# ArcadESP.net
KiCad netlist of a schematic drawn in EAGLE
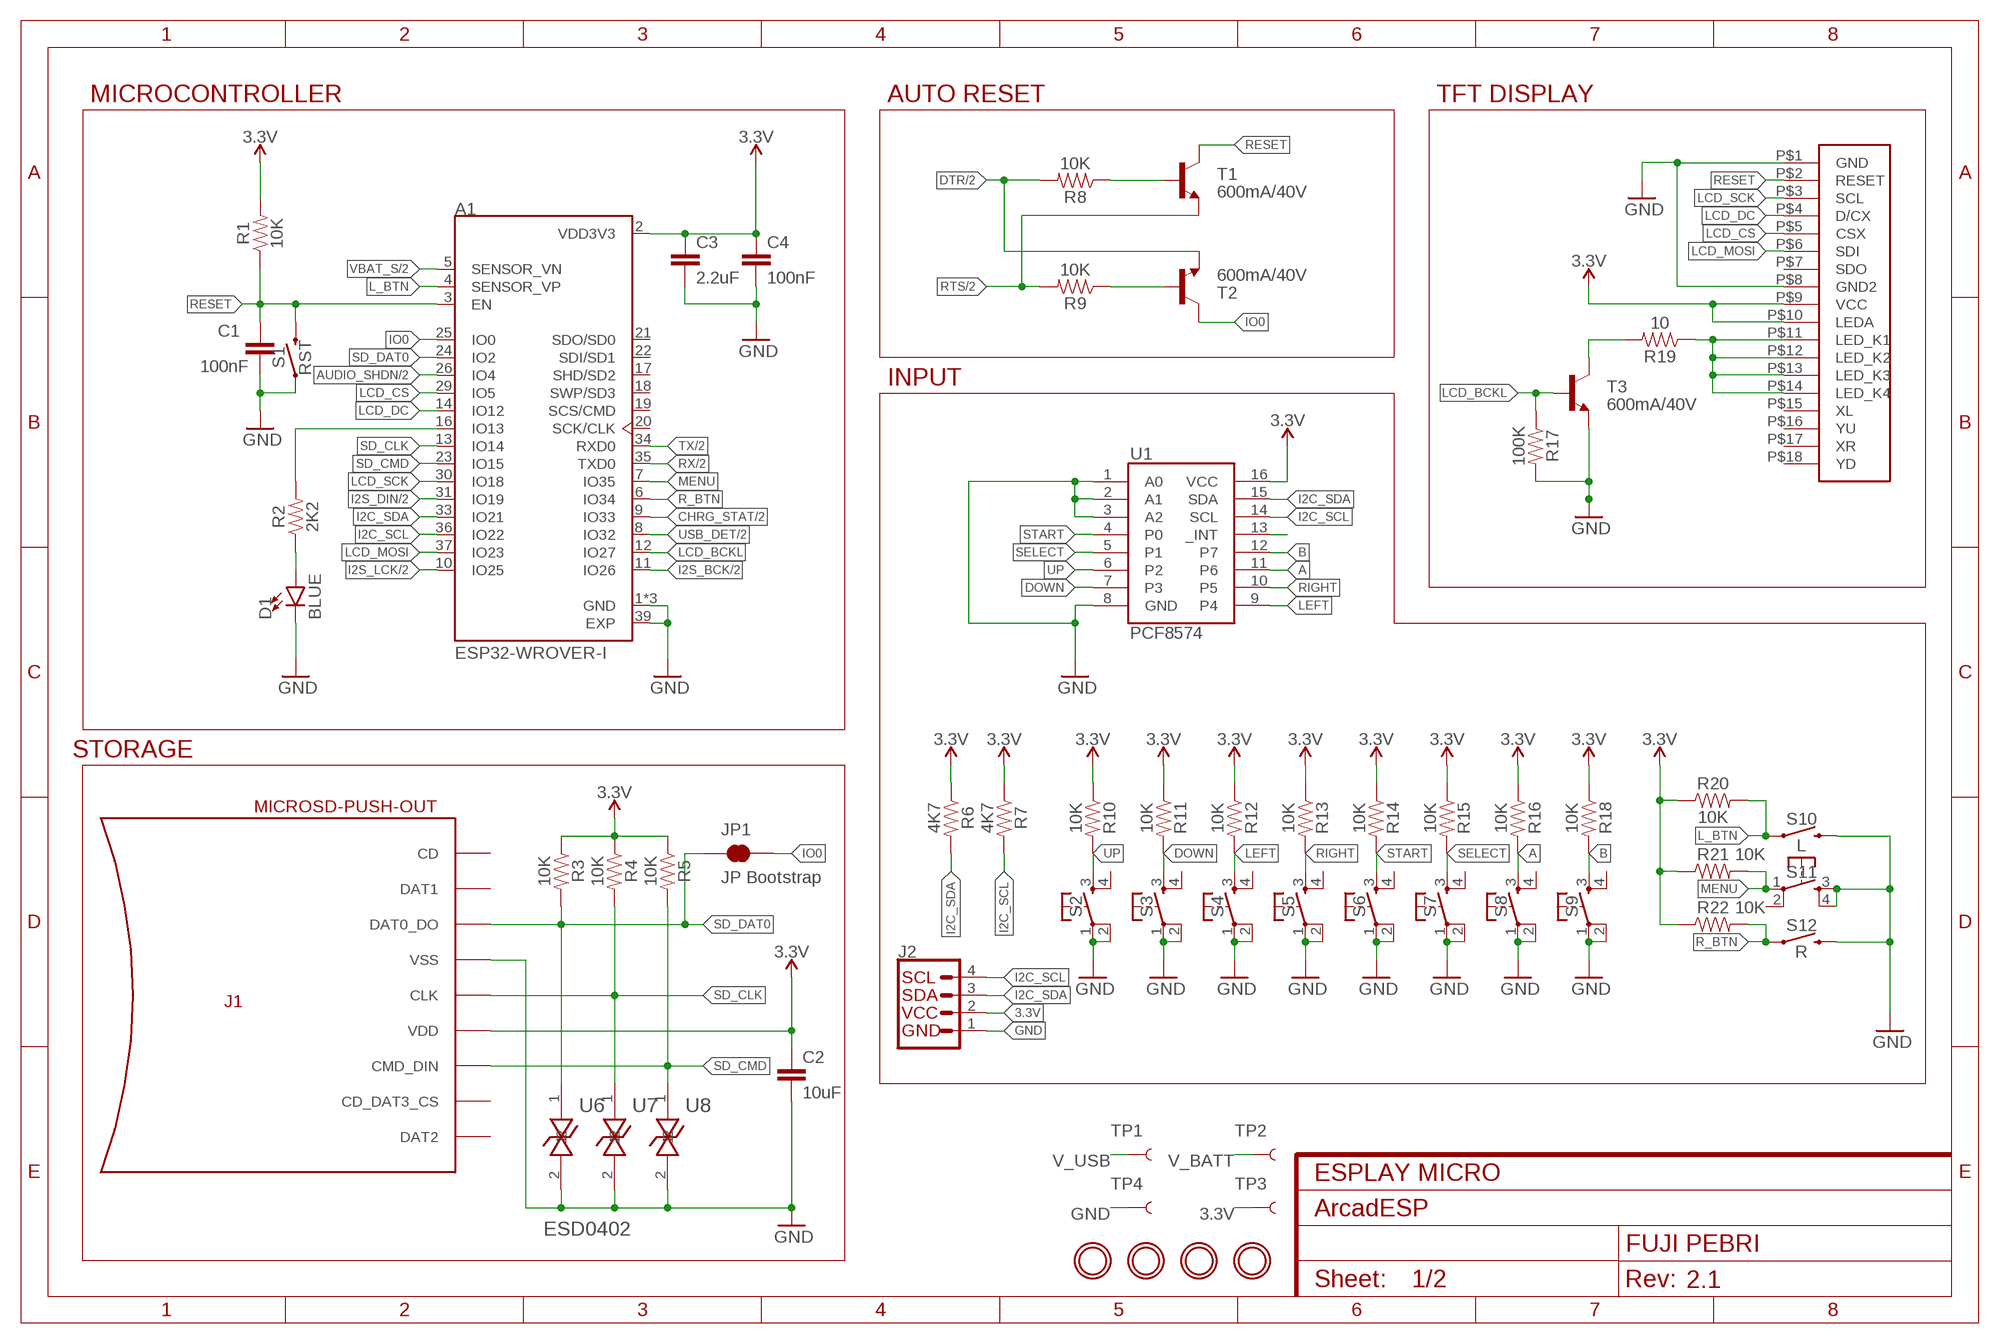
[diagram p0: schematic, sheet 1]
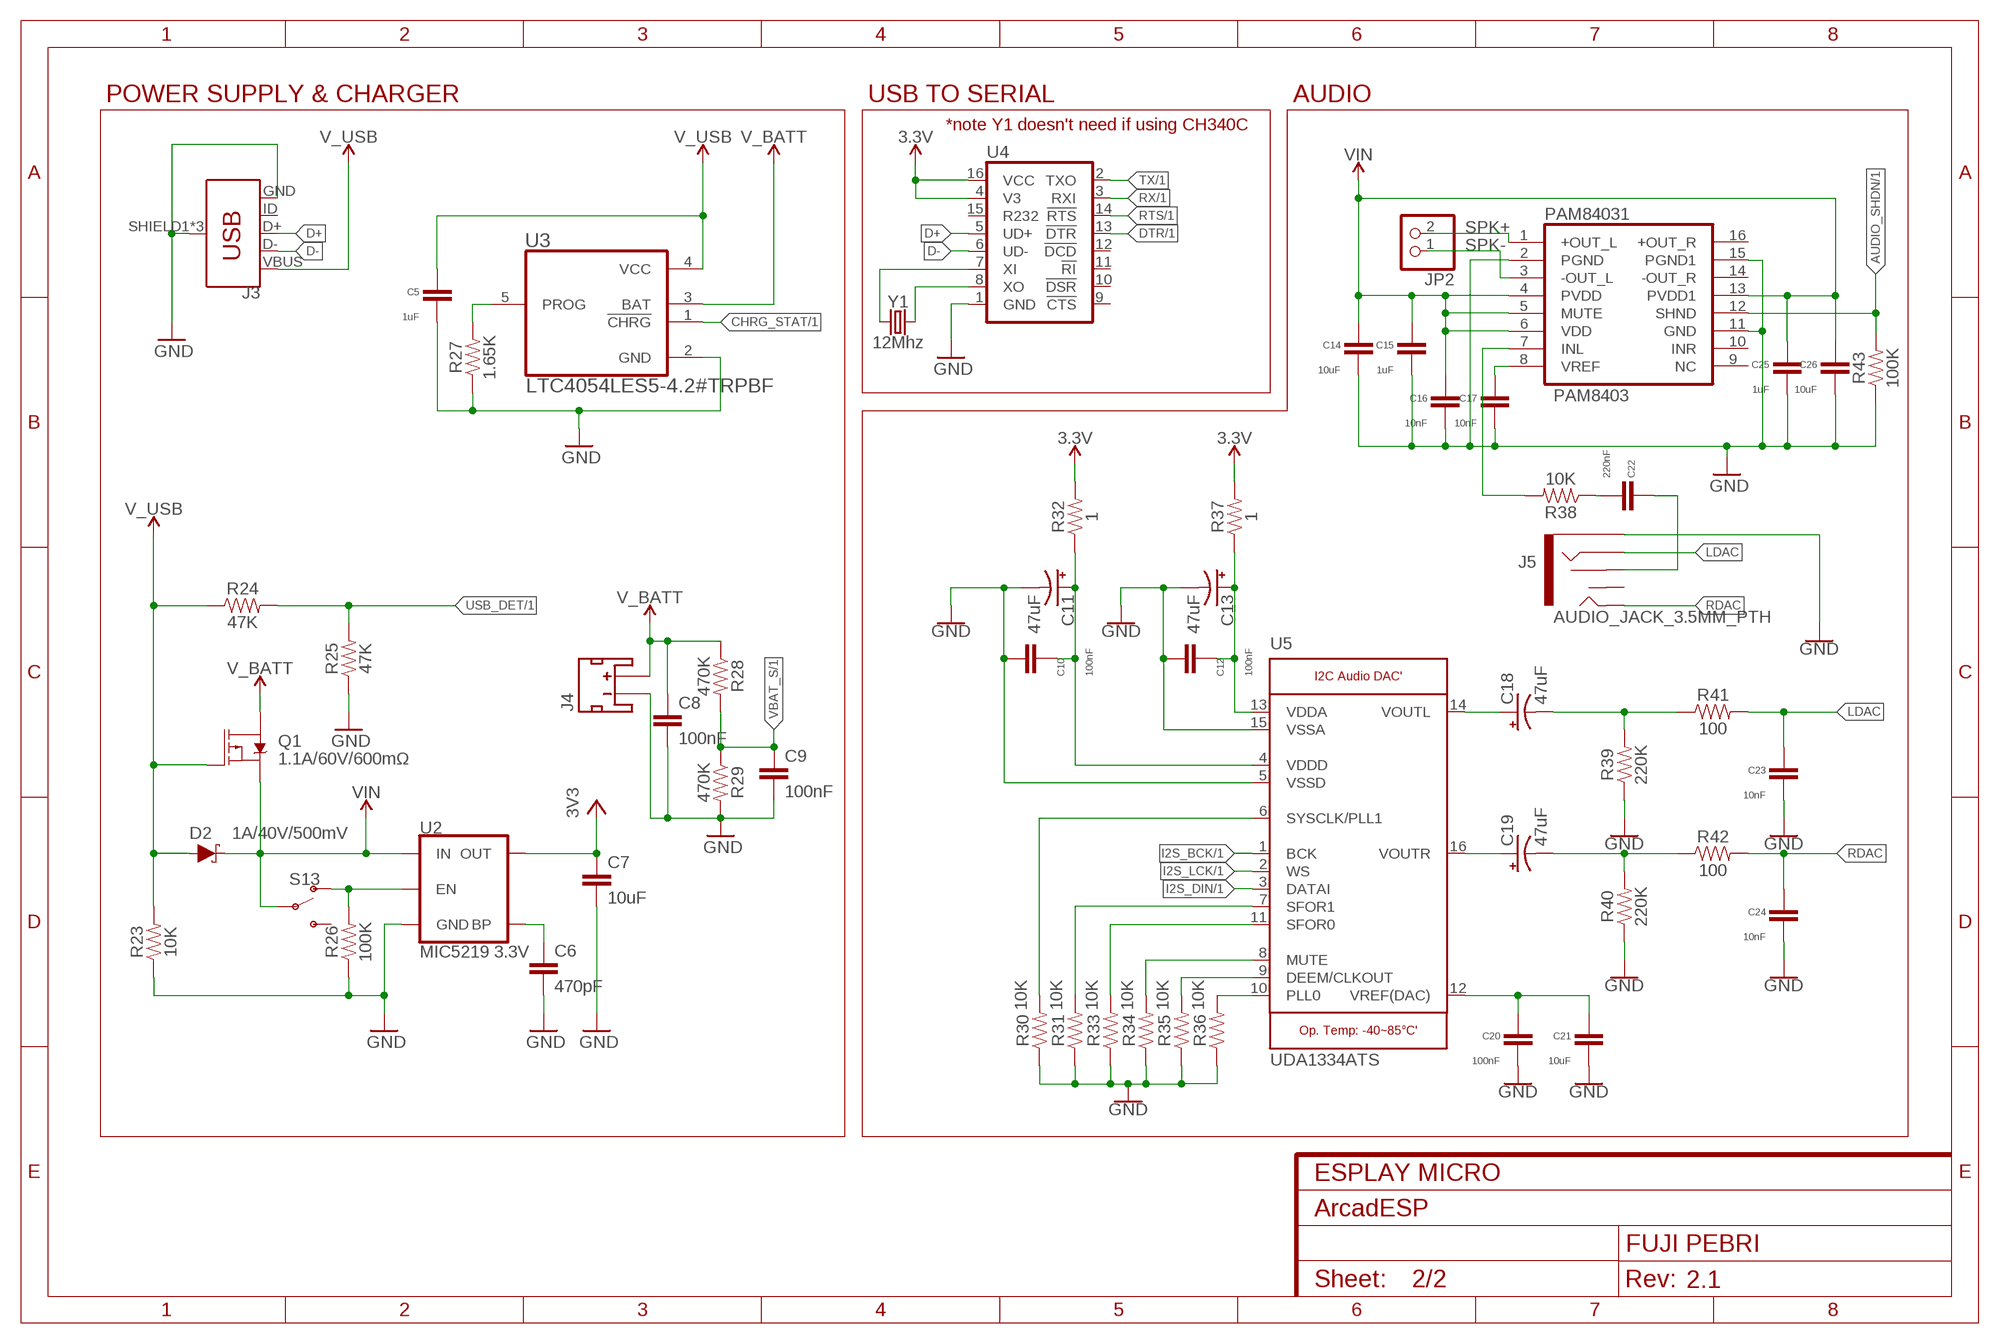
[diagram p1: schematic, sheet 2]

(export (version "E")
  (design (tool "Eeschema 10.0.6"))
  (components
    (comp (ref "C5")
      (value "1uF")
      (footprint "eagle-import:0805")
      (libsource (lib "eagle-import") (part "2.2UF-0805-25V-(+80/-20%)"))
    )
    (comp (ref "C6")
      (value "470pF")
      (footprint "eagle-import:0805")
      (libsource (lib "eagle-import") (part "2.2UF-0805-25V-(+80/-20%)"))
    )
    (comp (ref "C7")
      (value "10uF")
      (footprint "eagle-import:0805")
      (libsource (lib "eagle-import") (part "2.2UF-0805-25V-(+80/-20%)"))
    )
    (comp (ref "C8")
      (value "100nF")
      (footprint "eagle-import:0805")
      (libsource (lib "eagle-import") (part "2.2UF-0805-25V-(+80/-20%)"))
    )
    (comp (ref "C9")
      (value "100nF")
      (footprint "eagle-import:0805")
      (libsource (lib "eagle-import") (part "2.2UF-0805-25V-(+80/-20%)"))
    )
    (comp (ref "C10")
      (value "100nF")
      (footprint "eagle-import:0805")
      (libsource (lib "eagle-import") (part "2.2UF-0805-25V-(+80/-20%)"))
    )
    (comp (ref "C11")
      (value "47uF")
      (footprint "eagle-import:EIA3528")
      (libsource (lib "eagle-import") (part "47UF-POLAR-EIA3528-10V-10%"))
    )
    (comp (ref "C12")
      (value "100nF")
      (footprint "eagle-import:0805")
      (libsource (lib "eagle-import") (part "2.2UF-0805-25V-(+80/-20%)"))
    )
    (comp (ref "C13")
      (value "47uF")
      (footprint "eagle-import:EIA3528")
      (libsource (lib "eagle-import") (part "47UF-POLAR-EIA3528-10V-10%"))
    )
    (comp (ref "C14")
      (value "10uF")
      (footprint "eagle-import:0805")
      (libsource (lib "eagle-import") (part "2.2UF-0805-25V-(+80/-20%)"))
    )
    (comp (ref "C15")
      (value "1uF")
      (footprint "eagle-import:0805")
      (libsource (lib "eagle-import") (part "2.2UF-0805-25V-(+80/-20%)"))
    )
    (comp (ref "C16")
      (value "10nF")
      (footprint "eagle-import:0805")
      (libsource (lib "eagle-import") (part "2.2UF-0805-25V-(+80/-20%)"))
    )
    (comp (ref "C17")
      (value "10nF")
      (footprint "eagle-import:0805")
      (libsource (lib "eagle-import") (part "2.2UF-0805-25V-(+80/-20%)"))
    )
    (comp (ref "C18")
      (value "47uF")
      (footprint "eagle-import:EIA3528")
      (libsource (lib "eagle-import") (part "47UF-POLAR-EIA3528-10V-10%"))
    )
    (comp (ref "C19")
      (value "47uF")
      (footprint "eagle-import:EIA3528")
      (libsource (lib "eagle-import") (part "47UF-POLAR-EIA3528-10V-10%"))
    )
    (comp (ref "C20")
      (value "100nF")
      (footprint "eagle-import:0805")
      (libsource (lib "eagle-import") (part "2.2UF-0805-25V-(+80/-20%)"))
    )
    (comp (ref "C21")
      (value "10uF")
      (footprint "eagle-import:0805")
      (libsource (lib "eagle-import") (part "2.2UF-0805-25V-(+80/-20%)"))
    )
    (comp (ref "C22")
      (value "220nF")
      (footprint "eagle-import:0805")
      (libsource (lib "eagle-import") (part "2.2UF-0805-25V-(+80/-20%)"))
    )
    (comp (ref "C23")
      (value "10nF")
      (footprint "eagle-import:0805")
      (libsource (lib "eagle-import") (part "2.2UF-0805-25V-(+80/-20%)"))
    )
    (comp (ref "C24")
      (value "10nF")
      (footprint "eagle-import:0805")
      (libsource (lib "eagle-import") (part "2.2UF-0805-25V-(+80/-20%)"))
    )
    (comp (ref "C25")
      (value "1uF")
      (footprint "eagle-import:0805")
      (libsource (lib "eagle-import") (part "2.2UF-0805-25V-(+80/-20%)"))
    )
    (comp (ref "C26")
      (value "10uF")
      (footprint "eagle-import:0805")
      (libsource (lib "eagle-import") (part "2.2UF-0805-25V-(+80/-20%)"))
    )
    (comp (ref "D2")
      (value "1A/40V/500mV")
      (footprint "eagle-import:SMA-DIODE")
      (libsource (lib "eagle-import") (part "DIODE-SCHOTTKY-SS14"))
    )
    (comp (ref "J3")
      (value "USB_MICRO-B_FEMALE-SMT")
      (footprint "eagle-import:USB-B-MICRO-SMD")
      (libsource (lib "eagle-import") (part "USB_MICRO-B_FEMALE-SMT"))
    )
    (comp (ref "J4")
      (value "JST_2MM_MALE")
      (footprint "eagle-import:JST-2-SMD")
      (libsource (lib "eagle-import") (part "JST_2MM_MALE"))
    )
    (comp (ref "J5")
      (value "AUDIO_JACK_3.5MM_PTH")
      (footprint "eagle-import:AUDIO-JACK")
      (libsource (lib "eagle-import") (part "AUDIO_JACK_3.5MM_PTH"))
    )
    (comp (ref "JP2")
      (value "PINHD-1X2_2.00")
      (footprint "eagle-import:1X02M")
      (libsource (lib "eagle-import") (part "PINHD-1X2_2.00"))
    )
    (comp (ref "PAM84031")
      (value "PAM8403")
      (footprint "eagle-import:SOP-16")
      (libsource (lib "eagle-import") (part "PAM8403"))
    )
    (comp (ref "Q1")
      (value "1.1A/60V/600mΩ")
      (footprint "eagle-import:SOT23-3")
      (libsource (lib "eagle-import") (part "MOSFET_PCH-SI2309DS"))
    )
    (comp (ref "R23")
      (value "10K")
      (footprint "eagle-import:0805")
      (libsource (lib "eagle-import") (part "0.22OHM-0805-1/4W-1%"))
    )
    (comp (ref "R24")
      (value "47K")
      (footprint "eagle-import:0805")
      (libsource (lib "eagle-import") (part "0.22OHM-0805-1/4W-1%"))
    )
    (comp (ref "R25")
      (value "47K")
      (footprint "eagle-import:0805")
      (libsource (lib "eagle-import") (part "0.22OHM-0805-1/4W-1%"))
    )
    (comp (ref "R26")
      (value "100K")
      (footprint "eagle-import:0805")
      (libsource (lib "eagle-import") (part "0.22OHM-0805-1/4W-1%"))
    )
    (comp (ref "R27")
      (value "1.65K")
      (footprint "eagle-import:0805")
      (libsource (lib "eagle-import") (part "0.3OHM-0805-1/8W-1%"))
    )
    (comp (ref "R28")
      (value "470K")
      (footprint "eagle-import:0805")
      (libsource (lib "eagle-import") (part "0.22OHM-0805-1/4W-1%"))
    )
    (comp (ref "R29")
      (value "470K")
      (footprint "eagle-import:0805")
      (libsource (lib "eagle-import") (part "0.22OHM-0805-1/4W-1%"))
    )
    (comp (ref "R30")
      (value "10K")
      (footprint "eagle-import:0805")
      (libsource (lib "eagle-import") (part "0.3OHM-0805-1/8W-1%"))
    )
    (comp (ref "R31")
      (value "10K")
      (footprint "eagle-import:0805")
      (libsource (lib "eagle-import") (part "0.3OHM-0805-1/8W-1%"))
    )
    (comp (ref "R32")
      (value "1")
      (footprint "eagle-import:0805")
      (libsource (lib "eagle-import") (part "0.3OHM-0805-1/8W-1%"))
    )
    (comp (ref "R33")
      (value "10K")
      (footprint "eagle-import:0805")
      (libsource (lib "eagle-import") (part "0.3OHM-0805-1/8W-1%"))
    )
    (comp (ref "R34")
      (value "10K")
      (footprint "eagle-import:0805")
      (libsource (lib "eagle-import") (part "0.3OHM-0805-1/8W-1%"))
    )
    (comp (ref "R35")
      (value "10K")
      (footprint "eagle-import:0805")
      (libsource (lib "eagle-import") (part "0.3OHM-0805-1/8W-1%"))
    )
    (comp (ref "R36")
      (value "10K")
      (footprint "eagle-import:0805")
      (libsource (lib "eagle-import") (part "0.3OHM-0805-1/8W-1%"))
    )
    (comp (ref "R37")
      (value "1")
      (footprint "eagle-import:0805")
      (libsource (lib "eagle-import") (part "0.3OHM-0805-1/8W-1%"))
    )
    (comp (ref "R38")
      (value "10K")
      (footprint "eagle-import:0805")
      (libsource (lib "eagle-import") (part "0.3OHM-0805-1/8W-1%"))
    )
    (comp (ref "R39")
      (value "220K")
      (footprint "eagle-import:0805")
      (libsource (lib "eagle-import") (part "0.3OHM-0805-1/8W-1%"))
    )
    (comp (ref "R40")
      (value "220K")
      (footprint "eagle-import:0805")
      (libsource (lib "eagle-import") (part "0.3OHM-0805-1/8W-1%"))
    )
    (comp (ref "R41")
      (value "100")
      (footprint "eagle-import:0805")
      (libsource (lib "eagle-import") (part "0.3OHM-0805-1/8W-1%"))
    )
    (comp (ref "R42")
      (value "100")
      (footprint "eagle-import:0805")
      (libsource (lib "eagle-import") (part "0.3OHM-0805-1/8W-1%"))
    )
    (comp (ref "R43")
      (value "100K")
      (footprint "eagle-import:0805")
      (libsource (lib "eagle-import") (part "0.3OHM-0805-1/8W-1%"))
    )
    (comp (ref "S13")
      (value "SWITCH-SPDT-SMD-RIGHT-ANGLE")
      (footprint "eagle-import:SWITCH_SPST_SMD_A")
      (libsource (lib "eagle-import") (part "SWITCH-SPDT-SMD-RIGHT-ANGLE"))
    )
    (comp (ref "U2")
      (value "MIC5219 3.3V")
      (footprint "eagle-import:SOT23-5")
      (libsource (lib "eagle-import") (part "V_REG_MIC52193.3V"))
    )
    (comp (ref "U3")
      (value "LTC4054LES5-4.2#TRPBF")
      (footprint "eagle-import:SOT95P280X100-5N")
      (fields
        (field (name "DIGI-KEY_PART_NUMBER") "LTC4054LES5-4.2#TRPBFCT-ND")
        (field (name "MF") "Linear Technology/Analog")
      )
      (libsource (lib "eagle-import") (part "LTC4054LES5-4.2#TRPBF"))
    )
    (comp (ref "U4")
      (value "CH340G")
      (footprint "eagle-import:SO016")
      (libsource (lib "eagle-import") (part "CH340GSMD"))
    )
    (comp (ref "U5")
      (value "UDA1334ATS")
      (footprint "eagle-import:MICROBUILDER_SSOP16_4.4MM")
      (libsource (lib "eagle-import") (part "MICROBUILDER_AUDIO_I2S_UDA1334{dblquote}{dblquote}"))
    )
    (comp (ref "Y1")
      (value "12Mhz")
      (footprint "eagle-import:CRYSTAL-SMD-5X3.2-4PAD")
      (libsource (lib "eagle-import") (part "CRYSTALSMD-5X3.2-4PAD"))
    )
    (comp (ref "A1")
      (value "ESP32-WROVER-I")
      (footprint "eagle-import:XCVR_ESP32-WROVER-I")
      (fields (field (name "MF") "Espressif Systems"))
      (libsource (lib "eagle-import") (part "ESP32-WROVER-I"))
    )
    (comp (ref "C1")
      (value "100nF")
      (footprint "eagle-import:0805")
      (libsource (lib "eagle-import") (part "2.2UF-0805-25V-(+80/-20%)"))
    )
    (comp (ref "C2")
      (value "10uF")
      (footprint "eagle-import:0805")
      (libsource (lib "eagle-import") (part "2.2UF-0805-25V-(+80/-20%)"))
    )
    (comp (ref "C3")
      (value "2.2uF")
      (footprint "eagle-import:0805")
      (libsource (lib "eagle-import") (part "2.2UF-0805-25V-(+80/-20%)"))
    )
    (comp (ref "C4")
      (value "100nF")
      (footprint "eagle-import:0805")
      (libsource (lib "eagle-import") (part "2.2UF-0805-25V-(+80/-20%)"))
    )
    (comp (ref "D1")
      (value "BLUE")
      (footprint "eagle-import:LED-0603")
      (libsource (lib "eagle-import") (part "LED-BLUE0603"))
    )
    (comp (ref "H1")
      (value "MICROBUILDER_MOUNTINGHOLE3.0THIN")
      (footprint "eagle-import:MICROBUILDER_MOUNTINGHOLE_3.0_PLATEDTHIN")
      (libsource (lib "eagle-import") (part "MICROBUILDER_MOUNTINGHOLE3.0THIN"))
    )
    (comp (ref "H2")
      (value "MICROBUILDER_MOUNTINGHOLE3.0THIN")
      (footprint "eagle-import:MICROBUILDER_MOUNTINGHOLE_3.0_PLATEDTHIN")
      (libsource (lib "eagle-import") (part "MICROBUILDER_MOUNTINGHOLE3.0THIN"))
    )
    (comp (ref "H3")
      (value "MICROBUILDER_MOUNTINGHOLE3.0THIN")
      (footprint "eagle-import:MICROBUILDER_MOUNTINGHOLE_3.0_PLATEDTHIN")
      (libsource (lib "eagle-import") (part "MICROBUILDER_MOUNTINGHOLE3.0THIN"))
    )
    (comp (ref "H4")
      (value "MICROBUILDER_MOUNTINGHOLE3.0THIN")
      (footprint "eagle-import:MICROBUILDER_MOUNTINGHOLE_3.0_PLATEDTHIN")
      (libsource (lib "eagle-import") (part "MICROBUILDER_MOUNTINGHOLE3.0THIN"))
    )
    (comp (ref "J1")
      (value "MICROSD-PUSH-OUT")
      (footprint "eagle-import:MICROSD-PUSH-OUT")
      (libsource (lib "eagle-import") (part "MICROSD-PUSH-OUT"))
    )
    (comp (ref "J2")
      (value "QWIIC_CONNECTORJS-1MM")
      (footprint "eagle-import:1X04_1MM_RA")
      (libsource (lib "eagle-import") (part "QWIIC_CONNECTORJS-1MM"))
    )
    (comp (ref "JP1")
      (value "JP Bootstrap")
      (footprint "eagle-import:SMT-JUMPER_2_NC_TRACE_NO-SILK")
      (libsource (lib "eagle-import") (part "JUMPER-SMT_2_NC_TRACE_NO-SILK"))
    )
    (comp (ref "LCD1")
      (value "ILI9341-2.4")
      (footprint "eagle-import:ILI9341-2.4")
      (libsource (lib "eagle-import") (part "ILI9341-2.4"))
    )
    (comp (ref "R1")
      (value "10K")
      (footprint "eagle-import:0805")
      (libsource (lib "eagle-import") (part "0.22OHM-0805-1/4W-1%"))
    )
    (comp (ref "R2")
      (value "2K2")
      (footprint "eagle-import:0805")
      (libsource (lib "eagle-import") (part "0.22OHM-0805-1/4W-1%"))
    )
    (comp (ref "R3")
      (value "10K")
      (footprint "eagle-import:0805")
      (libsource (lib "eagle-import") (part "0.22OHM-0805-1/4W-1%"))
    )
    (comp (ref "R4")
      (value "10K")
      (footprint "eagle-import:0805")
      (libsource (lib "eagle-import") (part "0.22OHM-0805-1/4W-1%"))
    )
    (comp (ref "R5")
      (value "10K")
      (footprint "eagle-import:0805")
      (libsource (lib "eagle-import") (part "0.22OHM-0805-1/4W-1%"))
    )
    (comp (ref "R6")
      (value "4K7")
      (footprint "eagle-import:0805")
      (libsource (lib "eagle-import") (part "0.22OHM-0805-1/4W-1%"))
    )
    (comp (ref "R7")
      (value "4K7")
      (footprint "eagle-import:0805")
      (libsource (lib "eagle-import") (part "0.22OHM-0805-1/4W-1%"))
    )
    (comp (ref "R8")
      (value "10K")
      (footprint "eagle-import:0805")
      (libsource (lib "eagle-import") (part "0.22OHM-0805-1/4W-1%"))
    )
    (comp (ref "R9")
      (value "10K")
      (footprint "eagle-import:0805")
      (libsource (lib "eagle-import") (part "0.22OHM-0805-1/4W-1%"))
    )
    (comp (ref "R10")
      (value "10K")
      (footprint "eagle-import:0805")
      (libsource (lib "eagle-import") (part "0.22OHM-0805-1/4W-1%"))
    )
    (comp (ref "R11")
      (value "10K")
      (footprint "eagle-import:0805")
      (libsource (lib "eagle-import") (part "0.22OHM-0805-1/4W-1%"))
    )
    (comp (ref "R12")
      (value "10K")
      (footprint "eagle-import:0805")
      (libsource (lib "eagle-import") (part "0.22OHM-0805-1/4W-1%"))
    )
    (comp (ref "R13")
      (value "10K")
      (footprint "eagle-import:0805")
      (libsource (lib "eagle-import") (part "0.22OHM-0805-1/4W-1%"))
    )
    (comp (ref "R14")
      (value "10K")
      (footprint "eagle-import:0805")
      (libsource (lib "eagle-import") (part "0.22OHM-0805-1/4W-1%"))
    )
    (comp (ref "R15")
      (value "10K")
      (footprint "eagle-import:0805")
      (libsource (lib "eagle-import") (part "0.22OHM-0805-1/4W-1%"))
    )
    (comp (ref "R16")
      (value "10K")
      (footprint "eagle-import:0805")
      (libsource (lib "eagle-import") (part "0.22OHM-0805-1/4W-1%"))
    )
    (comp (ref "R17")
      (value "100K")
      (footprint "eagle-import:0805")
      (libsource (lib "eagle-import") (part "0.22OHM-0805-1/4W-1%"))
    )
    (comp (ref "R18")
      (value "10K")
      (footprint "eagle-import:0805")
      (libsource (lib "eagle-import") (part "0.22OHM-0805-1/4W-1%"))
    )
    (comp (ref "R19")
      (value "10")
      (footprint "eagle-import:0805")
      (libsource (lib "eagle-import") (part "0.22OHM-0805-1/4W-1%"))
    )
    (comp (ref "R20")
      (value "10K")
      (footprint "eagle-import:0805")
      (libsource (lib "eagle-import") (part "0.22OHM-0805-1/4W-1%"))
    )
    (comp (ref "R21")
      (value "10K")
      (footprint "eagle-import:0805")
      (libsource (lib "eagle-import") (part "0.22OHM-0805-1/4W-1%"))
    )
    (comp (ref "R22")
      (value "10K")
      (footprint "eagle-import:0805")
      (libsource (lib "eagle-import") (part "0.22OHM-0805-1/4W-1%"))
    )
    (comp (ref "S1")
      (value "RST")
      (footprint "eagle-import:TACTILE_SWITCH_SMD_4.6X2.8MM")
      (libsource (lib "eagle-import") (part "MOMENTARY-SWITCH-SPST-SMD-4.6X2.8MM"))
    )
    (comp (ref "S2")
      (value "MOMENTARY-SWITCH-SPST-2-SMD-5.2MM")
      (footprint "eagle-import:TACTILE_SWITCH_SMD_5.2MM")
      (libsource (lib "eagle-import") (part "MOMENTARY-SWITCH-SPST-2-SMD-5.2MM"))
    )
    (comp (ref "S3")
      (value "MOMENTARY-SWITCH-SPST-2-SMD-5.2MM")
      (footprint "eagle-import:TACTILE_SWITCH_SMD_5.2MM")
      (libsource (lib "eagle-import") (part "MOMENTARY-SWITCH-SPST-2-SMD-5.2MM"))
    )
    (comp (ref "S4")
      (value "MOMENTARY-SWITCH-SPST-2-SMD-5.2MM")
      (footprint "eagle-import:TACTILE_SWITCH_SMD_5.2MM")
      (libsource (lib "eagle-import") (part "MOMENTARY-SWITCH-SPST-2-SMD-5.2MM"))
    )
    (comp (ref "S5")
      (value "MOMENTARY-SWITCH-SPST-2-SMD-5.2MM")
      (footprint "eagle-import:TACTILE_SWITCH_SMD_5.2MM")
      (libsource (lib "eagle-import") (part "MOMENTARY-SWITCH-SPST-2-SMD-5.2MM"))
    )
    (comp (ref "S6")
      (value "MOMENTARY-SWITCH-SPST-2-SMD-5.2MM")
      (footprint "eagle-import:TACTILE_SWITCH_SMD_5.2MM")
      (libsource (lib "eagle-import") (part "MOMENTARY-SWITCH-SPST-2-SMD-5.2MM"))
    )
    (comp (ref "S7")
      (value "MOMENTARY-SWITCH-SPST-2-SMD-5.2MM")
      (footprint "eagle-import:TACTILE_SWITCH_SMD_5.2MM")
      (libsource (lib "eagle-import") (part "MOMENTARY-SWITCH-SPST-2-SMD-5.2MM"))
    )
    (comp (ref "S8")
      (value "MOMENTARY-SWITCH-SPST-2-SMD-5.2MM")
      (footprint "eagle-import:TACTILE_SWITCH_SMD_5.2MM")
      (libsource (lib "eagle-import") (part "MOMENTARY-SWITCH-SPST-2-SMD-5.2MM"))
    )
    (comp (ref "S9")
      (value "MOMENTARY-SWITCH-SPST-2-SMD-5.2MM")
      (footprint "eagle-import:TACTILE_SWITCH_SMD_5.2MM")
      (libsource (lib "eagle-import") (part "MOMENTARY-SWITCH-SPST-2-SMD-5.2MM"))
    )
    (comp (ref "S10")
      (value "L")
      (footprint "eagle-import:TACTILE_SWITCH_PTH_RIGHT_ANGLE_KIT")
      (libsource (lib "eagle-import") (part "MOMENTARY-SWITCH-SPST-PTH-RIGHT-ANGLE-KIT"))
    )
    (comp (ref "S11")
      (value "MOMENTARY-SWITCH-SPST-2-SMD-5.2MM")
      (footprint "eagle-import:TACTILE_SWITCH_SMD_5.2MM")
      (libsource (lib "eagle-import") (part "MOMENTARY-SWITCH-SPST-2-SMD-5.2MM"))
    )
    (comp (ref "S12")
      (value "R")
      (footprint "eagle-import:TACTILE_SWITCH_PTH_RIGHT_ANGLE_KIT")
      (libsource (lib "eagle-import") (part "MOMENTARY-SWITCH-SPST-PTH-RIGHT-ANGLE-KIT"))
    )
    (comp (ref "T1")
      (value "600mA/40V")
      (footprint "eagle-import:SOT23-3")
      (libsource (lib "eagle-import") (part "TRANS_NPN-MMBT2222AL"))
    )
    (comp (ref "T2")
      (value "600mA/40V")
      (footprint "eagle-import:SOT23-3")
      (libsource (lib "eagle-import") (part "TRANS_NPN-MMBT2222AL"))
    )
    (comp (ref "T3")
      (value "600mA/40V")
      (footprint "eagle-import:SOT23-3")
      (libsource (lib "eagle-import") (part "TRANS_NPN-MMBT2222AL"))
    )
    (comp (ref "TP1")
      (value "TEST-POINT3")
      (footprint "eagle-import:PAD.03X.03")
      (libsource (lib "eagle-import") (part "TEST-POINT3"))
    )
    (comp (ref "TP2")
      (value "TEST-POINT3")
      (footprint "eagle-import:PAD.03X.03")
      (libsource (lib "eagle-import") (part "TEST-POINT3"))
    )
    (comp (ref "TP3")
      (value "TEST-POINT3")
      (footprint "eagle-import:PAD.03X.03")
      (libsource (lib "eagle-import") (part "TEST-POINT3"))
    )
    (comp (ref "TP4")
      (value "TEST-POINT3")
      (footprint "eagle-import:PAD.03X.03")
      (libsource (lib "eagle-import") (part "TEST-POINT3"))
    )
    (comp (ref "U1")
      (value "PCF8574")
      (footprint "eagle-import:SO16")
      (fields (field (name "MF") "Texas Instruments"))
      (libsource (lib "eagle-import") (part "PCF8574"))
    )
    (comp (ref "U6")
      (value "ESD0402")
      (footprint "eagle-import:ESD0402")
      (libsource (lib "eagle-import") (part "ESD0402"))
    )
    (comp (ref "U7")
      (value "ESD0402")
      (footprint "eagle-import:ESD0402")
      (libsource (lib "eagle-import") (part "ESD0402"))
    )
    (comp (ref "U8")
      (value "ESD0402")
      (footprint "eagle-import:ESD0402")
      (libsource (lib "eagle-import") (part "ESD0402"))
    )
  )
  (nets
    (net (code "1") (name "3.3V") (class "Default")
      (node (ref "A1") (pin "2") (pinfunction "VDD3V3_2") (pintype "power_in"))
      (node (ref "C2") (pin "1") (pinfunction "1_1") (pintype "passive"))
      (node (ref "C3") (pin "1") (pinfunction "1_1") (pintype "passive"))
      (node (ref "C4") (pin "1") (pinfunction "1_1") (pintype "passive"))
      (node (ref "C7") (pin "1") (pinfunction "1_1") (pintype "passive"))
      (node (ref "J1") (pin "4") (pinfunction "VDD_4") (pintype "bidirectional"))
      (node (ref "J2") (pin "2") (pinfunction "2_2") (pintype "power_in"))
      (node (ref "LCD1") (pin "P$10") (pinfunction "LEDA_P$10") (pintype "bidirectional"))
      (node (ref "LCD1") (pin "P$9") (pinfunction "VCC_P$9") (pintype "bidirectional"))
      (node (ref "R1") (pin "2") (pinfunction "2_2") (pintype "passive"))
      (node (ref "R10") (pin "1") (pinfunction "1_1") (pintype "passive"))
      (node (ref "R11") (pin "1") (pinfunction "1_1") (pintype "passive"))
      (node (ref "R12") (pin "1") (pinfunction "1_1") (pintype "passive"))
      (node (ref "R13") (pin "1") (pinfunction "1_1") (pintype "passive"))
      (node (ref "R14") (pin "1") (pinfunction "1_1") (pintype "passive"))
      (node (ref "R15") (pin "1") (pinfunction "1_1") (pintype "passive"))
      (node (ref "R16") (pin "1") (pinfunction "1_1") (pintype "passive"))
      (node (ref "R18") (pin "1") (pinfunction "1_1") (pintype "passive"))
      (node (ref "R20") (pin "1") (pinfunction "1_1") (pintype "passive"))
      (node (ref "R21") (pin "1") (pinfunction "1_1") (pintype "passive"))
      (node (ref "R22") (pin "1") (pinfunction "1_1") (pintype "passive"))
      (node (ref "R3") (pin "1") (pinfunction "1_1") (pintype "passive"))
      (node (ref "R32") (pin "2") (pinfunction "2_2") (pintype "passive"))
      (node (ref "R37") (pin "2") (pinfunction "2_2") (pintype "passive"))
      (node (ref "R4") (pin "1") (pinfunction "1_1") (pintype "passive"))
      (node (ref "R5") (pin "1") (pinfunction "1_1") (pintype "passive"))
      (node (ref "R6") (pin "1") (pinfunction "1_1") (pintype "passive"))
      (node (ref "R7") (pin "1") (pinfunction "1_1") (pintype "passive"))
      (node (ref "TP3") (pin "P$1") (pinfunction "1_P$1") (pintype "bidirectional"))
      (node (ref "U1") (pin "16") (pinfunction "VCC_16") (pintype "bidirectional"))
      (node (ref "U2") (pin "5") (pinfunction "OUT_5") (pintype "passive"))
      (node (ref "U4") (pin "16") (pinfunction "VCC_16") (pintype "bidirectional"))
      (node (ref "U4") (pin "4") (pinfunction "V3_4") (pintype "bidirectional"))
    )
    (net (code "2") (name "A") (class "Default")
      (node (ref "R16") (pin "2") (pinfunction "2_2") (pintype "passive"))
      (node (ref "S8") (pin "3") (pinfunction "3_3") (pintype "passive"))
      (node (ref "U1") (pin "11") (pinfunction "P6_11") (pintype "bidirectional"))
    )
    (net (code "3") (name "AUDIO_SHDN") (class "Default")
      (node (ref "A1") (pin "26") (pinfunction "IO4_26") (pintype "bidirectional"))
      (node (ref "PAM84031") (pin "12") (pinfunction "SHND_12") (pintype "output"))
      (node (ref "R43") (pin "2") (pinfunction "2_2") (pintype "passive"))
    )
    (net (code "4") (name "B") (class "Default")
      (node (ref "R18") (pin "2") (pinfunction "2_2") (pintype "passive"))
      (node (ref "S9") (pin "3") (pinfunction "3_3") (pintype "passive"))
      (node (ref "U1") (pin "12") (pinfunction "P7_12") (pintype "bidirectional"))
    )
    (net (code "5") (name "CHRG_STAT") (class "Default")
      (node (ref "A1") (pin "9") (pinfunction "IO33_9") (pintype "bidirectional"))
      (node (ref "U3") (pin "1") (pinfunction "~{CHRG}_1") (pintype "output"))
    )
    (net (code "6") (name "D+") (class "Default")
      (node (ref "J3") (pin "D+") (pinfunction "D+_D+") (pintype "bidirectional"))
      (node (ref "U4") (pin "5") (pinfunction "UD+_5") (pintype "bidirectional"))
    )
    (net (code "7") (name "D-") (class "Default")
      (node (ref "J3") (pin "D-") (pinfunction "D-_D-") (pintype "bidirectional"))
      (node (ref "U4") (pin "6") (pinfunction "UD-_6") (pintype "bidirectional"))
    )
    (net (code "8") (name "DOWN") (class "Default")
      (node (ref "R11") (pin "2") (pinfunction "2_2") (pintype "passive"))
      (node (ref "S3") (pin "3") (pinfunction "3_3") (pintype "passive"))
      (node (ref "U1") (pin "7") (pinfunction "P3_7") (pintype "bidirectional"))
    )
    (net (code "9") (name "DTR") (class "Default")
      (node (ref "R8") (pin "2") (pinfunction "2_2") (pintype "passive"))
      (node (ref "T2") (pin "2") (pinfunction "E_2") (pintype "passive"))
      (node (ref "U4") (pin "13") (pinfunction "~{DTR}_13") (pintype "bidirectional"))
    )
    (net (code "10") (name "GND") (class "Default")
      (node (ref "A1") (pin "1") (pinfunction "GND_1") (pintype "power_in"))
      (node (ref "A1") (pin "15") (pinfunction "GND_15") (pintype "power_in"))
      (node (ref "A1") (pin "38") (pinfunction "GND_38") (pintype "power_in"))
      (node (ref "A1") (pin "39") (pinfunction "EXP_39") (pintype "power_in"))
      (node (ref "C1") (pin "2") (pinfunction "2_2") (pintype "passive"))
      (node (ref "C10") (pin "1") (pinfunction "1_1") (pintype "passive"))
      (node (ref "C11") (pin "C") (pinfunction "-_C") (pintype "passive"))
      (node (ref "C12") (pin "1") (pinfunction "1_1") (pintype "passive"))
      (node (ref "C13") (pin "C") (pinfunction "-_C") (pintype "passive"))
      (node (ref "C14") (pin "1") (pinfunction "1_1") (pintype "passive"))
      (node (ref "C15") (pin "1") (pinfunction "1_1") (pintype "passive"))
      (node (ref "C16") (pin "1") (pinfunction "1_1") (pintype "passive"))
      (node (ref "C17") (pin "1") (pinfunction "1_1") (pintype "passive"))
      (node (ref "C2") (pin "2") (pinfunction "2_2") (pintype "passive"))
      (node (ref "C20") (pin "1") (pinfunction "1_1") (pintype "passive"))
      (node (ref "C21") (pin "1") (pinfunction "1_1") (pintype "passive"))
      (node (ref "C23") (pin "1") (pinfunction "1_1") (pintype "passive"))
      (node (ref "C24") (pin "1") (pinfunction "1_1") (pintype "passive"))
      (node (ref "C25") (pin "1") (pinfunction "1_1") (pintype "passive"))
      (node (ref "C26") (pin "1") (pinfunction "1_1") (pintype "passive"))
      (node (ref "C3") (pin "2") (pinfunction "2_2") (pintype "passive"))
      (node (ref "C4") (pin "2") (pinfunction "2_2") (pintype "passive"))
      (node (ref "C5") (pin "1") (pinfunction "1_1") (pintype "passive"))
      (node (ref "C6") (pin "2") (pinfunction "2_2") (pintype "passive"))
      (node (ref "C7") (pin "2") (pinfunction "2_2") (pintype "passive"))
      (node (ref "C8") (pin "2") (pinfunction "2_2") (pintype "passive"))
      (node (ref "C9") (pin "2") (pinfunction "2_2") (pintype "passive"))
      (node (ref "D1") (pin "C") (pinfunction "C_C") (pintype "passive"))
      (node (ref "J1") (pin "6") (pinfunction "VSS_6") (pintype "bidirectional"))
      (node (ref "J1") (pin "G1") (pinfunction "VSS_G1") (pintype "bidirectional"))
      (node (ref "J1") (pin "G2") (pinfunction "VSS_G2") (pintype "bidirectional"))
      (node (ref "J1") (pin "G3") (pinfunction "VSS_G3") (pintype "bidirectional"))
      (node (ref "J1") (pin "G4") (pinfunction "VSS_G4") (pintype "bidirectional"))
      (node (ref "J2") (pin "1") (pinfunction "1_1") (pintype "power_in"))
      (node (ref "J3") (pin "GND") (pinfunction "GND_GND") (pintype "power_in"))
      (node (ref "J3") (pin "SHIELD1") (pinfunction "SHIELD_SHIELD1") (pintype "bidirectional"))
      (node (ref "J3") (pin "SHIELD2") (pinfunction "SHIELD_SHIELD2") (pintype "bidirectional"))
      (node (ref "J3") (pin "SHIELD3") (pinfunction "SHIELD_SHIELD3") (pintype "bidirectional"))
      (node (ref "J4") (pin "1") (pinfunction "-_1") (pintype "bidirectional"))
      (node (ref "J5") (pin "SLEEVE") (pinfunction "SLEEVE_SLEEVE") (pintype "bidirectional"))
      (node (ref "LCD1") (pin "P$1") (pinfunction "GND_P$1") (pintype "bidirectional"))
      (node (ref "LCD1") (pin "P$8") (pinfunction "GND2_P$8") (pintype "bidirectional"))
      (node (ref "PAM84031") (pin "11") (pinfunction "GND_11") (pintype "output"))
      (node (ref "PAM84031") (pin "15") (pinfunction "PGND1_15") (pintype "output"))
      (node (ref "PAM84031") (pin "2") (pinfunction "PGND_2") (pintype "input"))
      (node (ref "R17") (pin "2") (pinfunction "2_2") (pintype "passive"))
      (node (ref "R23") (pin "1") (pinfunction "1_1") (pintype "passive"))
      (node (ref "R25") (pin "1") (pinfunction "1_1") (pintype "passive"))
      (node (ref "R26") (pin "1") (pinfunction "1_1") (pintype "passive"))
      (node (ref "R27") (pin "1") (pinfunction "1_1") (pintype "passive"))
      (node (ref "R29") (pin "2") (pinfunction "2_2") (pintype "passive"))
      (node (ref "R30") (pin "1") (pinfunction "1_1") (pintype "passive"))
      (node (ref "R31") (pin "1") (pinfunction "1_1") (pintype "passive"))
      (node (ref "R33") (pin "1") (pinfunction "1_1") (pintype "passive"))
      (node (ref "R34") (pin "1") (pinfunction "1_1") (pintype "passive"))
      (node (ref "R35") (pin "1") (pinfunction "1_1") (pintype "passive"))
      (node (ref "R36") (pin "1") (pinfunction "1_1") (pintype "passive"))
      (node (ref "R39") (pin "1") (pinfunction "1_1") (pintype "passive"))
      (node (ref "R40") (pin "1") (pinfunction "1_1") (pintype "passive"))
      (node (ref "R43") (pin "1") (pinfunction "1_1") (pintype "passive"))
      (node (ref "S1") (pin "1") (pinfunction "1_1") (pintype "passive"))
      (node (ref "S1") (pin "2") (pinfunction "1_2") (pintype "passive"))
      (node (ref "S10") (pin "2") (pinfunction "2_2") (pintype "passive"))
      (node (ref "S11") (pin "3") (pinfunction "3_3") (pintype "passive"))
      (node (ref "S11") (pin "4") (pinfunction "4_4") (pintype "passive"))
      (node (ref "S12") (pin "2") (pinfunction "2_2") (pintype "passive"))
      (node (ref "S2") (pin "1") (pinfunction "1_1") (pintype "passive"))
      (node (ref "S2") (pin "2") (pinfunction "2_2") (pintype "passive"))
      (node (ref "S3") (pin "1") (pinfunction "1_1") (pintype "passive"))
      (node (ref "S3") (pin "2") (pinfunction "2_2") (pintype "passive"))
      (node (ref "S4") (pin "1") (pinfunction "1_1") (pintype "passive"))
      (node (ref "S4") (pin "2") (pinfunction "2_2") (pintype "passive"))
      (node (ref "S5") (pin "1") (pinfunction "1_1") (pintype "passive"))
      (node (ref "S5") (pin "2") (pinfunction "2_2") (pintype "passive"))
      (node (ref "S6") (pin "1") (pinfunction "1_1") (pintype "passive"))
      (node (ref "S6") (pin "2") (pinfunction "2_2") (pintype "passive"))
      (node (ref "S7") (pin "1") (pinfunction "1_1") (pintype "passive"))
      (node (ref "S7") (pin "2") (pinfunction "2_2") (pintype "passive"))
      (node (ref "S8") (pin "1") (pinfunction "1_1") (pintype "passive"))
      (node (ref "S8") (pin "2") (pinfunction "2_2") (pintype "passive"))
      (node (ref "S9") (pin "1") (pinfunction "1_1") (pintype "passive"))
      (node (ref "S9") (pin "2") (pinfunction "2_2") (pintype "passive"))
      (node (ref "T3") (pin "2") (pinfunction "E_2") (pintype "passive"))
      (node (ref "TP4") (pin "P$1") (pinfunction "1_P$1") (pintype "bidirectional"))
      (node (ref "U1") (pin "1") (pinfunction "A0_1") (pintype "bidirectional"))
      (node (ref "U1") (pin "2") (pinfunction "A1_2") (pintype "bidirectional"))
      (node (ref "U1") (pin "3") (pinfunction "A2_3") (pintype "bidirectional"))
      (node (ref "U1") (pin "8") (pinfunction "GND_8") (pintype "bidirectional"))
      (node (ref "U2") (pin "2") (pinfunction "GND_2") (pintype "input"))
      (node (ref "U3") (pin "2") (pinfunction "GND_2") (pintype "power_in"))
      (node (ref "U4") (pin "1") (pinfunction "GND_1") (pintype "bidirectional"))
      (node (ref "U5") (pin "15") (pinfunction "VSSA_15") (pintype "power_in"))
      (node (ref "U5") (pin "5") (pinfunction "VSSD_5") (pintype "power_in"))
      (node (ref "U6") (pin "2") (pinfunction "2_2") (pintype "bidirectional"))
      (node (ref "U7") (pin "2") (pinfunction "2_2") (pintype "bidirectional"))
      (node (ref "U8") (pin "2") (pinfunction "2_2") (pintype "bidirectional"))
    )
    (net (code "11") (name "I2C_SCL") (class "Default")
      (node (ref "A1") (pin "36") (pinfunction "IO22_36") (pintype "bidirectional"))
      (node (ref "J2") (pin "4") (pinfunction "4_4") (pintype "passive"))
      (node (ref "R7") (pin "2") (pinfunction "2_2") (pintype "passive"))
      (node (ref "U1") (pin "14") (pinfunction "SCL_14") (pintype "bidirectional"))
    )
    (net (code "12") (name "I2C_SDA") (class "Default")
      (node (ref "A1") (pin "33") (pinfunction "IO21_33") (pintype "bidirectional"))
      (node (ref "J2") (pin "3") (pinfunction "3_3") (pintype "passive"))
      (node (ref "R6") (pin "2") (pinfunction "2_2") (pintype "passive"))
      (node (ref "U1") (pin "15") (pinfunction "SDA_15") (pintype "bidirectional"))
    )
    (net (code "13") (name "I2S_BCK") (class "Default")
      (node (ref "A1") (pin "11") (pinfunction "IO26_11") (pintype "bidirectional"))
      (node (ref "U5") (pin "1") (pinfunction "BCK_1") (pintype "input"))
    )
    (net (code "14") (name "I2S_DIN") (class "Default")
      (node (ref "A1") (pin "31") (pinfunction "IO19_31") (pintype "bidirectional"))
      (node (ref "U5") (pin "3") (pinfunction "DATAI_3") (pintype "input"))
    )
    (net (code "15") (name "I2S_LCK") (class "Default")
      (node (ref "A1") (pin "10") (pinfunction "IO25_10") (pintype "bidirectional"))
      (node (ref "U5") (pin "2") (pinfunction "WS_2") (pintype "input"))
    )
    (net (code "16") (name "IO0") (class "Default")
      (node (ref "A1") (pin "25") (pinfunction "IO0_25") (pintype "bidirectional"))
      (node (ref "JP1") (pin "2") (pinfunction "2_2") (pintype "passive"))
      (node (ref "T2") (pin "3") (pinfunction "C_3") (pintype "passive"))
    )
    (net (code "17") (name "LCD_BCKL") (class "Default")
      (node (ref "A1") (pin "12") (pinfunction "IO27_12") (pintype "bidirectional"))
      (node (ref "R17") (pin "1") (pinfunction "1_1") (pintype "passive"))
      (node (ref "T3") (pin "1") (pinfunction "B_1") (pintype "passive"))
    )
    (net (code "18") (name "LCD_CS") (class "Default")
      (node (ref "A1") (pin "29") (pinfunction "IO5_29") (pintype "bidirectional"))
      (node (ref "LCD1") (pin "P$5") (pinfunction "CSX_P$5") (pintype "bidirectional"))
    )
    (net (code "19") (name "LCD_DC") (class "Default")
      (node (ref "A1") (pin "14") (pinfunction "IO12_14") (pintype "bidirectional"))
      (node (ref "LCD1") (pin "P$4") (pinfunction "D/CX_P$4") (pintype "bidirectional"))
    )
    (net (code "20") (name "LCD_MOSI") (class "Default")
      (node (ref "A1") (pin "37") (pinfunction "IO23_37") (pintype "bidirectional"))
      (node (ref "LCD1") (pin "P$6") (pinfunction "SDI_P$6") (pintype "bidirectional"))
    )
    (net (code "21") (name "LCD_SCK") (class "Default")
      (node (ref "A1") (pin "30") (pinfunction "IO18_30") (pintype "bidirectional"))
      (node (ref "LCD1") (pin "P$3") (pinfunction "SCL_P$3") (pintype "bidirectional"))
    )
    (net (code "22") (name "LDAC") (class "Default")
      (node (ref "C23") (pin "2") (pinfunction "2_2") (pintype "passive"))
      (node (ref "J5") (pin "RING") (pinfunction "RING_RING") (pintype "bidirectional"))
      (node (ref "R41") (pin "2") (pinfunction "2_2") (pintype "passive"))
    )
    (net (code "23") (name "LEFT") (class "Default")
      (node (ref "R12") (pin "2") (pinfunction "2_2") (pintype "passive"))
      (node (ref "S4") (pin "3") (pinfunction "3_3") (pintype "passive"))
      (node (ref "U1") (pin "9") (pinfunction "P4_9") (pintype "bidirectional"))
    )
    (net (code "24") (name "L_BTN") (class "Default")
      (node (ref "A1") (pin "4") (pinfunction "SENSOR_VP_4") (pintype "input"))
      (node (ref "R20") (pin "2") (pinfunction "2_2") (pintype "passive"))
      (node (ref "S10") (pin "1") (pinfunction "1_1") (pintype "passive"))
    )
    (net (code "25") (name "MENU") (class "Default")
      (node (ref "A1") (pin "7") (pinfunction "IO35_7") (pintype "input"))
      (node (ref "R21") (pin "2") (pinfunction "2_2") (pintype "passive"))
      (node (ref "S11") (pin "1") (pinfunction "1_1") (pintype "passive"))
    )
    (net (code "26") (name "Net-(A1-IO13)") (class "Default")
      (node (ref "A1") (pin "16") (pinfunction "IO13_16") (pintype "bidirectional"))
      (node (ref "R2") (pin "2") (pinfunction "2_2") (pintype "passive"))
    )
    (net (code "27") (name "Net-(C11-+)") (class "Default")
      (node (ref "C10") (pin "2") (pinfunction "2_2") (pintype "passive"))
      (node (ref "C11") (pin "A") (pinfunction "+_A") (pintype "passive"))
      (node (ref "R32") (pin "1") (pinfunction "1_1") (pintype "passive"))
      (node (ref "U5") (pin "4") (pinfunction "VDDD_4") (pintype "power_in"))
    )
    (net (code "28") (name "Net-(C13-+)") (class "Default")
      (node (ref "C12") (pin "2") (pinfunction "2_2") (pintype "passive"))
      (node (ref "C13") (pin "A") (pinfunction "+_A") (pintype "passive"))
      (node (ref "R37") (pin "1") (pinfunction "1_1") (pintype "passive"))
      (node (ref "U5") (pin "13") (pinfunction "VDDA_13") (pintype "power_in"))
    )
    (net (code "29") (name "Net-(C18-+)") (class "Default")
      (node (ref "C18") (pin "A") (pinfunction "+_A") (pintype "passive"))
      (node (ref "U5") (pin "14") (pinfunction "VOUTL_14") (pintype "output"))
    )
    (net (code "30") (name "Net-(C18--)") (class "Default")
      (node (ref "C18") (pin "C") (pinfunction "-_C") (pintype "passive"))
      (node (ref "R39") (pin "2") (pinfunction "2_2") (pintype "passive"))
      (node (ref "R41") (pin "1") (pinfunction "1_1") (pintype "passive"))
    )
    (net (code "31") (name "Net-(C19-+)") (class "Default")
      (node (ref "C19") (pin "A") (pinfunction "+_A") (pintype "passive"))
      (node (ref "U5") (pin "16") (pinfunction "VOUTR_16") (pintype "output"))
    )
    (net (code "32") (name "Net-(C19--)") (class "Default")
      (node (ref "C19") (pin "C") (pinfunction "-_C") (pintype "passive"))
      (node (ref "R40") (pin "2") (pinfunction "2_2") (pintype "passive"))
      (node (ref "R42") (pin "1") (pinfunction "1_1") (pintype "passive"))
    )
    (net (code "33") (name "Net-(C22-Pad1)") (class "Default")
      (node (ref "C22") (pin "1") (pinfunction "1_1") (pintype "passive"))
      (node (ref "R38") (pin "1") (pinfunction "1_1") (pintype "passive"))
    )
    (net (code "34") (name "Net-(C22-Pad2)") (class "Default")
      (node (ref "C22") (pin "2") (pinfunction "2_2") (pintype "passive"))
      (node (ref "J5") (pin "RSH") (pinfunction "RSH_RSH") (pintype "bidirectional"))
    )
    (net (code "35") (name "Net-(D1-PadA)") (class "Default")
      (node (ref "D1") (pin "A") (pinfunction "A_A") (pintype "passive"))
      (node (ref "R2") (pin "1") (pinfunction "1_1") (pintype "passive"))
    )
    (net (code "36") (name "Net-(LCD1-LED_K1)") (class "Default")
      (node (ref "LCD1") (pin "P$11") (pinfunction "LED_K1_P$11") (pintype "bidirectional"))
      (node (ref "LCD1") (pin "P$12") (pinfunction "LED_K2_P$12") (pintype "bidirectional"))
      (node (ref "LCD1") (pin "P$13") (pinfunction "LED_K3_P$13") (pintype "bidirectional"))
      (node (ref "LCD1") (pin "P$14") (pinfunction "LED_K4_P$14") (pintype "bidirectional"))
      (node (ref "R19") (pin "1") (pinfunction "1_1") (pintype "passive"))
    )
    (net (code "37") (name "Net-(PAM84031-INL)") (class "Default")
      (node (ref "PAM84031") (pin "7") (pinfunction "INL_7") (pintype "input"))
      (node (ref "R38") (pin "2") (pinfunction "2_2") (pintype "passive"))
    )
    (net (code "38") (name "Net-(PAM84031-VREF)") (class "Default")
      (node (ref "C17") (pin "2") (pinfunction "2_2") (pintype "passive"))
      (node (ref "PAM84031") (pin "8") (pinfunction "VREF_8") (pintype "input"))
    )
    (net (code "39") (name "Net-(S13-O)") (class "Default")
      (node (ref "R26") (pin "2") (pinfunction "2_2") (pintype "passive"))
      (node (ref "S13") (pin "1") (pinfunction "O_1") (pintype "passive"))
      (node (ref "U2") (pin "3") (pinfunction "EN_3") (pintype "input"))
    )
    (net (code "40") (name "Net-(T1-B)") (class "Default")
      (node (ref "R8") (pin "1") (pinfunction "1_1") (pintype "passive"))
      (node (ref "T1") (pin "1") (pinfunction "B_1") (pintype "passive"))
    )
    (net (code "41") (name "Net-(T2-B)") (class "Default")
      (node (ref "R9") (pin "1") (pinfunction "1_1") (pintype "passive"))
      (node (ref "T2") (pin "1") (pinfunction "B_1") (pintype "passive"))
    )
    (net (code "42") (name "Net-(T3-C)") (class "Default")
      (node (ref "R19") (pin "2") (pinfunction "2_2") (pintype "passive"))
      (node (ref "T3") (pin "3") (pinfunction "C_3") (pintype "passive"))
    )
    (net (code "43") (name "Net-(U2-BP)") (class "Default")
      (node (ref "C6") (pin "1") (pinfunction "1_1") (pintype "passive"))
      (node (ref "U2") (pin "4") (pinfunction "BP_4") (pintype "input"))
    )
    (net (code "44") (name "Net-(U3-PROG)") (class "Default")
      (node (ref "R27") (pin "2") (pinfunction "2_2") (pintype "passive"))
      (node (ref "U3") (pin "5") (pinfunction "PROG_5") (pintype "input"))
    )
    (net (code "45") (name "Net-(U4-XI)") (class "Default")
      (node (ref "U4") (pin "7") (pinfunction "XI_7") (pintype "bidirectional"))
      (node (ref "Y1") (pin "3") (pinfunction "2_3") (pintype "passive"))
    )
    (net (code "46") (name "Net-(U4-XO)") (class "Default")
      (node (ref "U4") (pin "8") (pinfunction "XO_8") (pintype "bidirectional"))
      (node (ref "Y1") (pin "1") (pinfunction "1_1") (pintype "passive"))
    )
    (net (code "47") (name "Net-(U5-DEEM{slash}CLKOUT)") (class "Default")
      (node (ref "R35") (pin "2") (pinfunction "2_2") (pintype "passive"))
      (node (ref "U5") (pin "9") (pinfunction "DEEM/CLKOUT_9") (pintype "bidirectional"))
    )
    (net (code "48") (name "Net-(U5-MUTE)") (class "Default")
      (node (ref "R34") (pin "2") (pinfunction "2_2") (pintype "passive"))
      (node (ref "U5") (pin "8") (pinfunction "MUTE_8") (pintype "input"))
    )
    (net (code "49") (name "Net-(U5-PLL0)") (class "Default")
      (node (ref "R36") (pin "2") (pinfunction "2_2") (pintype "passive"))
      (node (ref "U5") (pin "10") (pinfunction "PLL0_10") (pintype "input"))
    )
    (net (code "50") (name "Net-(U5-SFOR0)") (class "Default")
      (node (ref "R33") (pin "2") (pinfunction "2_2") (pintype "passive"))
      (node (ref "U5") (pin "11") (pinfunction "SFOR0_11") (pintype "input"))
    )
    (net (code "51") (name "Net-(U5-SFOR1)") (class "Default")
      (node (ref "R31") (pin "2") (pinfunction "2_2") (pintype "passive"))
      (node (ref "U5") (pin "7") (pinfunction "SFOR1_7") (pintype "input"))
    )
    (net (code "52") (name "Net-(U5-SYSCLK{slash}PLL1)") (class "Default")
      (node (ref "R30") (pin "2") (pinfunction "2_2") (pintype "passive"))
      (node (ref "U5") (pin "6") (pinfunction "SYSCLK/PLL1_6") (pintype "input"))
    )
    (net (code "53") (name "Net-(U5-VREF(DAC))") (class "Default")
      (node (ref "C20") (pin "2") (pinfunction "2_2") (pintype "passive"))
      (node (ref "C21") (pin "2") (pinfunction "2_2") (pintype "passive"))
      (node (ref "U5") (pin "12") (pinfunction "VREF(DAC)_12") (pintype "output"))
    )
    (net (code "54") (name "RDAC") (class "Default")
      (node (ref "C24") (pin "2") (pinfunction "2_2") (pintype "passive"))
      (node (ref "J5") (pin "TIP") (pinfunction "TIP_TIP") (pintype "bidirectional"))
      (node (ref "R42") (pin "2") (pinfunction "2_2") (pintype "passive"))
    )
    (net (code "55") (name "RESET") (class "Default")
      (node (ref "A1") (pin "3") (pinfunction "EN_3") (pintype "input"))
      (node (ref "C1") (pin "1") (pinfunction "1_1") (pintype "passive"))
      (node (ref "LCD1") (pin "P$2") (pinfunction "RESET_P$2") (pintype "bidirectional"))
      (node (ref "R1") (pin "1") (pinfunction "1_1") (pintype "passive"))
      (node (ref "S1") (pin "3") (pinfunction "2_3") (pintype "passive"))
      (node (ref "S1") (pin "4") (pinfunction "2_4") (pintype "passive"))
      (node (ref "T1") (pin "3") (pinfunction "C_3") (pintype "passive"))
    )
    (net (code "56") (name "RIGHT") (class "Default")
      (node (ref "R13") (pin "2") (pinfunction "2_2") (pintype "passive"))
      (node (ref "S5") (pin "3") (pinfunction "3_3") (pintype "passive"))
      (node (ref "U1") (pin "10") (pinfunction "P5_10") (pintype "bidirectional"))
    )
    (net (code "57") (name "RTS") (class "Default")
      (node (ref "R9") (pin "2") (pinfunction "2_2") (pintype "passive"))
      (node (ref "T1") (pin "2") (pinfunction "E_2") (pintype "passive"))
      (node (ref "U4") (pin "14") (pinfunction "~{RTS}_14") (pintype "bidirectional"))
    )
    (net (code "58") (name "RX") (class "Default")
      (node (ref "A1") (pin "35") (pinfunction "TXD0_35") (pintype "bidirectional"))
      (node (ref "U4") (pin "3") (pinfunction "RXI_3") (pintype "bidirectional"))
    )
    (net (code "59") (name "R_BTN") (class "Default")
      (node (ref "A1") (pin "6") (pinfunction "IO34_6") (pintype "input"))
      (node (ref "R22") (pin "2") (pinfunction "2_2") (pintype "passive"))
      (node (ref "S12") (pin "1") (pinfunction "1_1") (pintype "passive"))
    )
    (net (code "60") (name "SD_CLK") (class "Default")
      (node (ref "A1") (pin "13") (pinfunction "IO14_13") (pintype "bidirectional"))
      (node (ref "J1") (pin "5") (pinfunction "CLK_5") (pintype "bidirectional"))
      (node (ref "R4") (pin "2") (pinfunction "2_2") (pintype "passive"))
      (node (ref "U7") (pin "1") (pinfunction "1_1") (pintype "bidirectional"))
    )
    (net (code "61") (name "SD_CMD") (class "Default")
      (node (ref "A1") (pin "23") (pinfunction "IO15_23") (pintype "bidirectional"))
      (node (ref "J1") (pin "3") (pinfunction "CMD_DIN_3") (pintype "bidirectional"))
      (node (ref "R5") (pin "2") (pinfunction "2_2") (pintype "passive"))
      (node (ref "U8") (pin "1") (pinfunction "1_1") (pintype "bidirectional"))
    )
    (net (code "62") (name "SD_DAT0") (class "Default")
      (node (ref "A1") (pin "24") (pinfunction "IO2_24") (pintype "bidirectional"))
      (node (ref "J1") (pin "7") (pinfunction "DAT0_DO_7") (pintype "bidirectional"))
      (node (ref "JP1") (pin "1") (pinfunction "1_1") (pintype "passive"))
      (node (ref "R3") (pin "2") (pinfunction "2_2") (pintype "passive"))
      (node (ref "U6") (pin "1") (pinfunction "1_1") (pintype "bidirectional"))
    )
    (net (code "63") (name "SELECT") (class "Default")
      (node (ref "R15") (pin "2") (pinfunction "2_2") (pintype "passive"))
      (node (ref "S7") (pin "3") (pinfunction "3_3") (pintype "passive"))
      (node (ref "U1") (pin "5") (pinfunction "P1_5") (pintype "bidirectional"))
    )
    (net (code "64") (name "SPK+") (class "Default")
      (node (ref "JP2") (pin "2") (pinfunction "2_2") (pintype "passive"))
      (node (ref "PAM84031") (pin "1") (pinfunction "+OUT_L_1") (pintype "input"))
    )
    (net (code "65") (name "SPK-") (class "Default")
      (node (ref "JP2") (pin "1") (pinfunction "1_1") (pintype "passive"))
      (node (ref "PAM84031") (pin "3") (pinfunction "-OUT_L_3") (pintype "input"))
    )
    (net (code "66") (name "START") (class "Default")
      (node (ref "R14") (pin "2") (pinfunction "2_2") (pintype "passive"))
      (node (ref "S6") (pin "3") (pinfunction "3_3") (pintype "passive"))
      (node (ref "U1") (pin "4") (pinfunction "P0_4") (pintype "bidirectional"))
    )
    (net (code "67") (name "TX") (class "Default")
      (node (ref "A1") (pin "34") (pinfunction "RXD0_34") (pintype "bidirectional"))
      (node (ref "U4") (pin "2") (pinfunction "TXO_2") (pintype "bidirectional"))
    )
    (net (code "68") (name "UP") (class "Default")
      (node (ref "R10") (pin "2") (pinfunction "2_2") (pintype "passive"))
      (node (ref "S2") (pin "3") (pinfunction "3_3") (pintype "passive"))
      (node (ref "U1") (pin "6") (pinfunction "P2_6") (pintype "bidirectional"))
    )
    (net (code "69") (name "USB_DET") (class "Default")
      (node (ref "A1") (pin "8") (pinfunction "IO32_8") (pintype "bidirectional"))
      (node (ref "R24") (pin "2") (pinfunction "2_2") (pintype "passive"))
      (node (ref "R25") (pin "2") (pinfunction "2_2") (pintype "passive"))
    )
    (net (code "70") (name "VBAT_S") (class "Default")
      (node (ref "A1") (pin "5") (pinfunction "SENSOR_VN_5") (pintype "input"))
      (node (ref "C9") (pin "1") (pinfunction "1_1") (pintype "passive"))
      (node (ref "R28") (pin "2") (pinfunction "2_2") (pintype "passive"))
      (node (ref "R29") (pin "1") (pinfunction "1_1") (pintype "passive"))
    )
    (net (code "71") (name "VIN") (class "Default")
      (node (ref "C14") (pin "2") (pinfunction "2_2") (pintype "passive"))
      (node (ref "C15") (pin "2") (pinfunction "2_2") (pintype "passive"))
      (node (ref "C16") (pin "2") (pinfunction "2_2") (pintype "passive"))
      (node (ref "C25") (pin "2") (pinfunction "2_2") (pintype "passive"))
      (node (ref "C26") (pin "2") (pinfunction "2_2") (pintype "passive"))
      (node (ref "D2") (pin "C") (pinfunction "C_C") (pintype "passive"))
      (node (ref "PAM84031") (pin "13") (pinfunction "PVDD1_13") (pintype "output"))
      (node (ref "PAM84031") (pin "4") (pinfunction "PVDD_4") (pintype "input"))
      (node (ref "PAM84031") (pin "5") (pinfunction "MUTE_5") (pintype "input"))
      (node (ref "PAM84031") (pin "6") (pinfunction "VDD_6") (pintype "input"))
      (node (ref "Q1") (pin "2") (pinfunction "S_2") (pintype "bidirectional"))
      (node (ref "S13") (pin "2") (pinfunction "P_2") (pintype "passive"))
      (node (ref "U2") (pin "1") (pinfunction "IN_1") (pintype "input"))
    )
    (net (code "72") (name "V_BATT") (class "Default")
      (node (ref "C8") (pin "1") (pinfunction "1_1") (pintype "passive"))
      (node (ref "J4") (pin "2") (pinfunction "+_2") (pintype "bidirectional"))
      (node (ref "Q1") (pin "3") (pinfunction "D_3") (pintype "bidirectional"))
      (node (ref "R28") (pin "1") (pinfunction "1_1") (pintype "passive"))
      (node (ref "TP2") (pin "P$1") (pinfunction "1_P$1") (pintype "bidirectional"))
      (node (ref "U3") (pin "3") (pinfunction "BAT_3") (pintype "output"))
    )
    (net (code "73") (name "V_USB") (class "Default")
      (node (ref "C5") (pin "2") (pinfunction "2_2") (pintype "passive"))
      (node (ref "D2") (pin "A") (pinfunction "A_A") (pintype "passive"))
      (node (ref "J3") (pin "VBUS") (pinfunction "VBUS_VBUS") (pintype "power_in"))
      (node (ref "Q1") (pin "1") (pinfunction "G_1") (pintype "bidirectional"))
      (node (ref "R23") (pin "2") (pinfunction "2_2") (pintype "passive"))
      (node (ref "R24") (pin "1") (pinfunction "1_1") (pintype "passive"))
      (node (ref "TP1") (pin "P$1") (pinfunction "1_P$1") (pintype "bidirectional"))
      (node (ref "U3") (pin "4") (pinfunction "VCC_4") (pintype "power_in"))
    )
    (net (code "74") (name "unconnected-(A1-SCK{slash}CLK-Pad20)") (class "Default")
      (node (ref "A1") (pin "20") (pinfunction "SCK/CLK_20") (pintype "bidirectional"))
    )
    (net (code "75") (name "unconnected-(A1-SCS{slash}CMD-Pad19)") (class "Default")
      (node (ref "A1") (pin "19") (pinfunction "SCS/CMD_19") (pintype "bidirectional"))
    )
    (net (code "76") (name "unconnected-(A1-SDI{slash}SD1-Pad22)") (class "Default")
      (node (ref "A1") (pin "22") (pinfunction "SDI/SD1_22") (pintype "bidirectional"))
    )
    (net (code "77") (name "unconnected-(A1-SDO{slash}SD0-Pad21)") (class "Default")
      (node (ref "A1") (pin "21") (pinfunction "SDO/SD0_21") (pintype "bidirectional"))
    )
    (net (code "78") (name "unconnected-(A1-SHD{slash}SD2-Pad17)") (class "Default")
      (node (ref "A1") (pin "17") (pinfunction "SHD/SD2_17") (pintype "bidirectional"))
    )
    (net (code "79") (name "unconnected-(A1-SWP{slash}SD3-Pad18)") (class "Default")
      (node (ref "A1") (pin "18") (pinfunction "SWP/SD3_18") (pintype "bidirectional"))
    )
    (net (code "80") (name "unconnected-(J1-CD_DAT3_CS-Pad2)") (class "Default")
      (node (ref "J1") (pin "2") (pinfunction "CD_DAT3_CS_2") (pintype "bidirectional"))
    )
    (net (code "81") (name "unconnected-(J1-DAT1-Pad8)") (class "Default")
      (node (ref "J1") (pin "8") (pinfunction "DAT1_8") (pintype "bidirectional"))
    )
    (net (code "82") (name "unconnected-(J1-DAT2-Pad1)") (class "Default")
      (node (ref "J1") (pin "1") (pinfunction "DAT2_1") (pintype "bidirectional"))
    )
    (net (code "83") (name "unconnected-(J1-PadCD)") (class "Default")
      (node (ref "J1") (pin "CD") (pinfunction "CD_CD") (pintype "bidirectional"))
    )
    (net (code "84") (name "unconnected-(J3-PadID)") (class "Default")
      (node (ref "J3") (pin "ID") (pinfunction "ID_ID") (pintype "bidirectional"))
    )
    (net (code "85") (name "unconnected-(J4-PAD1-PadNC1)") (class "Default")
      (node (ref "J4") (pin "NC1") (pinfunction "PAD1_NC1") (pintype "bidirectional"))
    )
    (net (code "86") (name "unconnected-(J4-PAD2-PadNC2)") (class "Default")
      (node (ref "J4") (pin "NC2") (pinfunction "PAD2_NC2") (pintype "bidirectional"))
    )
    (net (code "87") (name "unconnected-(J5-PadTSH)") (class "Default")
      (node (ref "J5") (pin "TSH") (pinfunction "TSH_TSH") (pintype "bidirectional"))
    )
    (net (code "88") (name "unconnected-(LCD1-SDO-PadP$7)") (class "Default")
      (node (ref "LCD1") (pin "P$7") (pinfunction "SDO_P$7") (pintype "bidirectional"))
    )
    (net (code "89") (name "unconnected-(LCD1-XL-PadP$15)") (class "Default")
      (node (ref "LCD1") (pin "P$15") (pinfunction "XL_P$15") (pintype "bidirectional"))
    )
    (net (code "90") (name "unconnected-(LCD1-XR-PadP$17)") (class "Default")
      (node (ref "LCD1") (pin "P$17") (pinfunction "XR_P$17") (pintype "bidirectional"))
    )
    (net (code "91") (name "unconnected-(LCD1-YD-PadP$18)") (class "Default")
      (node (ref "LCD1") (pin "P$18") (pinfunction "YD_P$18") (pintype "bidirectional"))
    )
    (net (code "92") (name "unconnected-(LCD1-YU-PadP$16)") (class "Default")
      (node (ref "LCD1") (pin "P$16") (pinfunction "YU_P$16") (pintype "bidirectional"))
    )
    (net (code "93") (name "unconnected-(PAM84031-+OUT_R-Pad16)") (class "Default")
      (node (ref "PAM84031") (pin "16") (pinfunction "+OUT_R_16") (pintype "output"))
    )
    (net (code "94") (name "unconnected-(PAM84031--OUT_R-Pad14)") (class "Default")
      (node (ref "PAM84031") (pin "14") (pinfunction "-OUT_R_14") (pintype "output"))
    )
    (net (code "95") (name "unconnected-(PAM84031-INR-Pad10)") (class "Default")
      (node (ref "PAM84031") (pin "10") (pinfunction "INR_10") (pintype "output"))
    )
    (net (code "96") (name "unconnected-(PAM84031-NC-Pad9)") (class "Default")
      (node (ref "PAM84031") (pin "9") (pinfunction "NC_9") (pintype "output"))
    )
    (net (code "97") (name "unconnected-(S2-Pad4)") (class "Default")
      (node (ref "S2") (pin "4") (pinfunction "4_4") (pintype "passive"))
    )
    (net (code "98") (name "unconnected-(S3-Pad4)") (class "Default")
      (node (ref "S3") (pin "4") (pinfunction "4_4") (pintype "passive"))
    )
    (net (code "99") (name "unconnected-(S4-Pad4)") (class "Default")
      (node (ref "S4") (pin "4") (pinfunction "4_4") (pintype "passive"))
    )
    (net (code "100") (name "unconnected-(S5-Pad4)") (class "Default")
      (node (ref "S5") (pin "4") (pinfunction "4_4") (pintype "passive"))
    )
    (net (code "101") (name "unconnected-(S6-Pad4)") (class "Default")
      (node (ref "S6") (pin "4") (pinfunction "4_4") (pintype "passive"))
    )
    (net (code "102") (name "unconnected-(S7-Pad4)") (class "Default")
      (node (ref "S7") (pin "4") (pinfunction "4_4") (pintype "passive"))
    )
    (net (code "103") (name "unconnected-(S8-Pad4)") (class "Default")
      (node (ref "S8") (pin "4") (pinfunction "4_4") (pintype "passive"))
    )
    (net (code "104") (name "unconnected-(S9-Pad4)") (class "Default")
      (node (ref "S9") (pin "4") (pinfunction "4_4") (pintype "passive"))
    )
    (net (code "105") (name "unconnected-(S11-Pad2)") (class "Default")
      (node (ref "S11") (pin "2") (pinfunction "2_2") (pintype "passive"))
    )
    (net (code "106") (name "unconnected-(S13-S-Pad3)") (class "Default")
      (node (ref "S13") (pin "3") (pinfunction "S_3") (pintype "passive"))
    )
    (net (code "107") (name "unconnected-(U1-_INT-Pad13)") (class "Default")
      (node (ref "U1") (pin "13") (pinfunction "_INT_13") (pintype "bidirectional"))
    )
    (net (code "108") (name "unconnected-(U4-R232-Pad15)") (class "Default")
      (node (ref "U4") (pin "15") (pinfunction "R232_15") (pintype "bidirectional"))
    )
    (net (code "109") (name "unconnected-(U4-~{CTS}-Pad9)") (class "Default")
      (node (ref "U4") (pin "9") (pinfunction "~{CTS}_9") (pintype "bidirectional"))
    )
    (net (code "110") (name "unconnected-(U4-~{DCD}-Pad12)") (class "Default")
      (node (ref "U4") (pin "12") (pinfunction "~{DCD}_12") (pintype "bidirectional"))
    )
    (net (code "111") (name "unconnected-(U4-~{DSR}-Pad10)") (class "Default")
      (node (ref "U4") (pin "10") (pinfunction "~{DSR}_10") (pintype "bidirectional"))
    )
    (net (code "112") (name "unconnected-(U4-~{RI}-Pad11)") (class "Default")
      (node (ref "U4") (pin "11") (pinfunction "~{RI}_11") (pintype "bidirectional"))
    )
  )
)
